# DM1097_IMU.net
KiCad netlist of a schematic drawn in Altium Designer
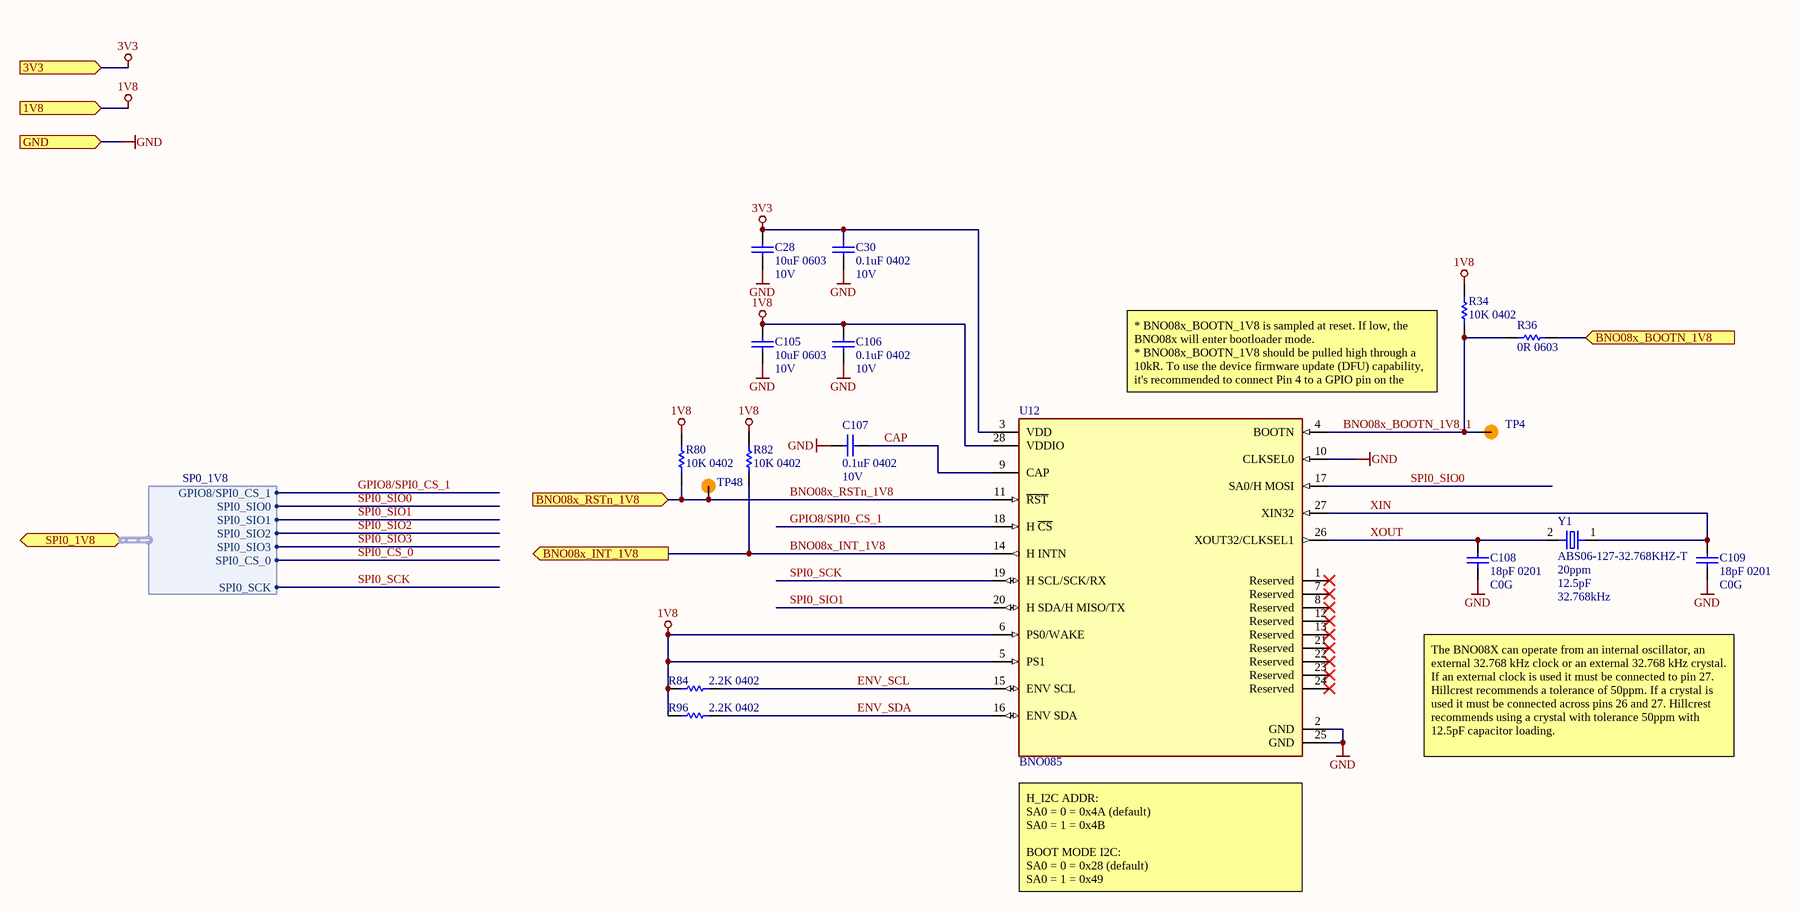
[diagram p0: DM1097_IMU.SchDoc]

(export (version "E")
  (design (tool "Eeschema 10.0.6"))
  (components
    (comp (ref "C28")
      (value "10uF 0603")
      (footprint "CAP_Altium_Vault_Generic:CAPC0603(1608)100_N")
      (description "CAP CER 10UF 10V X5R 0603 20%")
      (fields (field (name "TOLERANCE") "20%") (field (name "VOLTAGE RATING") "10V"))
      (libsource (lib "LuxonisMaster") (part "GRM188R61A106ME69D"))
    )
    (comp (ref "C30")
      (value "0.1uF 0402")
      (footprint "CAP_Altium_Vault_Generic:CAPC0402(1005)70_N")
      (description "CAP CER 0.1UF 10V X7R 0402 5%")
      (fields (field (name "TOLERANCE") "5%") (field (name "VOLTAGE RATING") "10V"))
      (libsource (lib "LuxonisMaster") (part "GRM155R71A104JA01D"))
    )
    (comp (ref "C105")
      (value "10uF 0603")
      (footprint "CAP_Altium_Vault_Generic:CAPC0603(1608)100_N")
      (description "CAP CER 10UF 10V X5R 0603 20%")
      (fields (field (name "TOLERANCE") "20%") (field (name "VOLTAGE RATING") "10V"))
      (libsource (lib "LuxonisMaster") (part "GRM188R61A106ME69D"))
    )
    (comp (ref "C106")
      (value "0.1uF 0402")
      (footprint "CAP_Altium_Vault_Generic:CAPC0402(1005)70_N")
      (description "CAP CER 0.1UF 10V X7R 0402 5%")
      (fields (field (name "TOLERANCE") "5%") (field (name "VOLTAGE RATING") "10V"))
      (libsource (lib "LuxonisMaster") (part "GRM155R71A104JA01D"))
    )
    (comp (ref "C107")
      (value "0.1uF 0402")
      (footprint "CAP_Altium_Vault_Generic:CAPC0402(1005)70_N")
      (description "CAP CER 0.1UF 10V X7R 0402 5%")
      (fields (field (name "TOLERANCE") "5%") (field (name "VOLTAGE RATING") "10V"))
      (libsource (lib "LuxonisMaster") (part "GRM155R71A104JA01D"))
    )
    (comp (ref "C108")
      (value "18pF 0201")
      (footprint "CAPC0201(0603)33_N")
      (description "Cap Ceramic 18pF 25V C0G 1% Pad SMD 0201 125C T/R")
      (fields (field (name "TOLERANCE") "1%") (field (name "DIELECTRIC") "C0G"))
      (libsource (lib "BW1092_R0M0E0") (part "GRM0335C1E180FA01D"))
    )
    (comp (ref "C109")
      (value "18pF 0201")
      (footprint "CAPC0201(0603)33_N")
      (description "Cap Ceramic 18pF 25V C0G 1% Pad SMD 0201 125C T/R")
      (fields (field (name "TOLERANCE") "1%") (field (name "DIELECTRIC") "C0G"))
      (libsource (lib "BW1092_R0M0E0") (part "GRM0335C1E180FA01D"))
    )
    (comp (ref "R34")
      (value "10K 0402")
      (footprint "RES_Altium_Vault_Generic:RESC0402(1005)_N")
      (fields (field (name "TOLERANCE") "1%"))
      (libsource (lib "LuxonisMaster") (part "RC0402FR-1310KL"))
    )
    (comp (ref "R36")
      (value "0R 0603")
      (footprint "RES_Altium_Vault_Generic:RESC0603(1608)_N")
      (fields (field (name "TOLERANCE") "5%"))
      (libsource (lib "LuxonisMaster") (part "CRCW06030000Z0EA"))
    )
    (comp (ref "R80")
      (value "10K 0402")
      (footprint "RES_Altium_Vault_Generic:RESC0402(1005)_N")
      (fields (field (name "TOLERANCE") "1%"))
      (libsource (lib "LuxonisMaster") (part "RC0402FR-1310KL"))
    )
    (comp (ref "R82")
      (value "10K 0402")
      (footprint "RES_Altium_Vault_Generic:RESC0402(1005)_N")
      (fields (field (name "TOLERANCE") "1%"))
      (libsource (lib "LuxonisMaster") (part "RC0402FR-1310KL"))
    )
    (comp (ref "R84")
      (value "2.2K 0402")
      (footprint "RES_Altium_Vault_Generic:RESC0402(1005)_N")
      (description "RES SMD 2.2K OHM 1% 1/16W 0402")
      (fields (field (name "TOLERANCE") "1%"))
      (libsource (lib "LuxonisMaster") (part "RC0402FR-072K2L"))
    )
    (comp (ref "R96")
      (value "2.2K 0402")
      (footprint "RES_Altium_Vault_Generic:RESC0402(1005)_N")
      (description "RES SMD 2.2K OHM 1% 1/16W 0402")
      (fields (field (name "TOLERANCE") "1%"))
      (libsource (lib "LuxonisMaster") (part "RC0402FR-072K2L"))
    )
    (comp (ref "TP4")
      (value "TP100_200_NS")
      (footprint "LuxonisMaster:TP100_200_NS")
      (libsource (lib "LuxonisMaster") (part "TEST_POINT"))
    )
    (comp (ref "TP48")
      (value "TP100_200_NS")
      (footprint "LuxonisMaster:TP100_200_NS")
      (libsource (lib "LuxonisMaster") (part "TEST_POINT"))
    )
    (comp (ref "U12")
      (value "BNO085")
      (footprint "LuxonisMaster:BNO085")
      (description "IMU ACCEL/GYRO/MAG I2C 32BIT")
      (libsource (lib "LuxonisMaster") (part "BNO085"))
    )
    (comp (ref "Y1")
      (value "ABS06-127-32.768KHZ-T")
      (footprint "LuxonisMaster:ABS06-127-32.768KHZ-T")
      (description "CRYSTAL 32.768kHz ±20ppm Crystal 12.5pF 90 kOhms 2-SMD, No Lead")
      (fields
        (field (name "FREQUENCY TOLERANCE") "20ppm")
        (field (name "LOAD CAPACITANCE") "12.5pF")
        (field (name "FREQUENCY") "32.768kHz")
      )
      (libsource (lib "LuxonisMaster") (part "ABS06-127-32.768KHZ-T"))
    )
  )
  (nets
    (net (code "2") (name "/BNO08x_BOOTN_1V8") (class "Default")
      (node (ref "R36") (pin "2") (pinfunction "2_2") (pintype "passive"))
    )
    (net (code "3") (name "/BNO08x_BOOTN_1V8_1") (class "Default")
      (node (ref "R34") (pin "1") (pinfunction "1_1") (pintype "passive"))
      (node (ref "R36") (pin "1") (pinfunction "1_1") (pintype "passive"))
      (node (ref "TP4") (pin "1") (pintype "passive"))
      (node (ref "U12") (pin "4") (pinfunction "BOOTN_4") (pintype "input"))
    )
    (net (code "4") (name "/BNO08x_INT_1V8") (class "Default")
      (node (ref "R82") (pin "1") (pinfunction "1_1") (pintype "passive"))
      (node (ref "U12") (pin "14") (pinfunction "H_INTN_14") (pintype "output"))
    )
    (net (code "5") (name "/BNO08x_RSTn_1V8") (class "Default")
      (node (ref "R80") (pin "1") (pinfunction "1_1") (pintype "passive"))
      (node (ref "TP48") (pin "1") (pintype "passive"))
      (node (ref "U12") (pin "11") (pinfunction "~{RST}_11") (pintype "input"))
    )
    (net (code "6") (name "/CAP") (class "Default")
      (node (ref "C107") (pin "1") (pinfunction "1_1") (pintype "passive"))
      (node (ref "U12") (pin "9") (pinfunction "CAP_9") (pintype "passive"))
    )
    (net (code "7") (name "/ENV_SCL") (class "Default")
      (node (ref "R84") (pin "2") (pinfunction "2_2") (pintype "passive"))
      (node (ref "U12") (pin "15") (pinfunction "ENV_SCL_15") (pintype "bidirectional"))
    )
    (net (code "8") (name "/ENV_SDA") (class "Default")
      (node (ref "R96") (pin "2") (pinfunction "2_2") (pintype "passive"))
      (node (ref "U12") (pin "16") (pinfunction "ENV_SDA_16") (pintype "bidirectional"))
    )
    (net (code "9") (name "/GPIO8{slash}SPI0_CS_1") (class "Default")
      (node (ref "U12") (pin "18") (pinfunction "H_~{CS}_18") (pintype "input"))
    )
    (net (code "11") (name "/SPI0_SCK") (class "Default")
      (node (ref "U12") (pin "19") (pinfunction "H_SCL/SCK/RX_19") (pintype "bidirectional"))
    )
    (net (code "12") (name "/SPI0_SIO0") (class "Default")
      (node (ref "U12") (pin "17") (pinfunction "SA0/H_MOSI_17") (pintype "input"))
    )
    (net (code "13") (name "/SPI0_SIO1") (class "Default")
      (node (ref "U12") (pin "20") (pinfunction "H_SDA/H_MISO/TX_20") (pintype "bidirectional"))
    )
    (net (code "16") (name "/XIN") (class "Default")
      (node (ref "C109") (pin "2") (pinfunction "2_2") (pintype "passive"))
      (node (ref "U12") (pin "27") (pinfunction "XIN32_27") (pintype "input"))
      (node (ref "Y1") (pin "1") (pinfunction "1_1") (pintype "passive"))
    )
    (net (code "17") (name "/XOUT") (class "Default")
      (node (ref "C108") (pin "2") (pinfunction "2_2") (pintype "passive"))
      (node (ref "U12") (pin "26") (pinfunction "XOUT32/CLKSEL1_26") (pintype "output"))
      (node (ref "Y1") (pin "2") (pinfunction "2_2") (pintype "passive"))
    )
    (net (code "19") (name "1V8") (class "Default")
      (node (ref "C105") (pin "2") (pinfunction "2_2") (pintype "passive"))
      (node (ref "C106") (pin "2") (pinfunction "2_2") (pintype "passive"))
      (node (ref "R34") (pin "2") (pinfunction "2_2") (pintype "passive"))
      (node (ref "R80") (pin "2") (pinfunction "2_2") (pintype "passive"))
      (node (ref "R82") (pin "2") (pinfunction "2_2") (pintype "passive"))
      (node (ref "R84") (pin "1") (pinfunction "1_1") (pintype "passive"))
      (node (ref "R96") (pin "1") (pinfunction "1_1") (pintype "passive"))
      (node (ref "U12") (pin "28") (pinfunction "VDDIO_28") (pintype "power_in"))
      (node (ref "U12") (pin "5") (pinfunction "PS1_5") (pintype "input"))
      (node (ref "U12") (pin "6") (pinfunction "PS0/WAKE_6") (pintype "input"))
    )
    (net (code "20") (name "3V3") (class "Default")
      (node (ref "C28") (pin "2") (pinfunction "2_2") (pintype "passive"))
      (node (ref "C30") (pin "2") (pinfunction "2_2") (pintype "passive"))
      (node (ref "U12") (pin "3") (pinfunction "VDD_3") (pintype "power_in"))
    )
    (net (code "21") (name "GND") (class "Default")
      (node (ref "C105") (pin "1") (pinfunction "1_1") (pintype "passive"))
      (node (ref "C106") (pin "1") (pinfunction "1_1") (pintype "passive"))
      (node (ref "C107") (pin "2") (pinfunction "2_2") (pintype "passive"))
      (node (ref "C108") (pin "1") (pinfunction "1_1") (pintype "passive"))
      (node (ref "C109") (pin "1") (pinfunction "1_1") (pintype "passive"))
      (node (ref "C28") (pin "1") (pinfunction "1_1") (pintype "passive"))
      (node (ref "C30") (pin "1") (pinfunction "1_1") (pintype "passive"))
      (node (ref "U12") (pin "10") (pinfunction "CLKSEL0_10") (pintype "input"))
      (node (ref "U12") (pin "2") (pinfunction "GND_2") (pintype "power_in"))
      (node (ref "U12") (pin "25") (pinfunction "GND_25") (pintype "power_in"))
    )
    (net (code "22") (name "unconnected-(U12-Reserved-Pad1)") (class "Default")
      (node (ref "U12") (pin "1") (pinfunction "Reserved_1") (pintype "passive+no_connect"))
    )
    (net (code "23") (name "unconnected-(U12-Reserved-Pad7)") (class "Default")
      (node (ref "U12") (pin "7") (pinfunction "Reserved_7") (pintype "passive+no_connect"))
    )
    (net (code "24") (name "unconnected-(U12-Reserved-Pad8)") (class "Default")
      (node (ref "U12") (pin "8") (pinfunction "Reserved_8") (pintype "passive+no_connect"))
    )
    (net (code "25") (name "unconnected-(U12-Reserved-Pad12)") (class "Default")
      (node (ref "U12") (pin "12") (pinfunction "Reserved_12") (pintype "passive+no_connect"))
    )
    (net (code "26") (name "unconnected-(U12-Reserved-Pad13)") (class "Default")
      (node (ref "U12") (pin "13") (pinfunction "Reserved_13") (pintype "passive+no_connect"))
    )
    (net (code "27") (name "unconnected-(U12-Reserved-Pad21)") (class "Default")
      (node (ref "U12") (pin "21") (pinfunction "Reserved_21") (pintype "passive+no_connect"))
    )
    (net (code "28") (name "unconnected-(U12-Reserved-Pad22)") (class "Default")
      (node (ref "U12") (pin "22") (pinfunction "Reserved_22") (pintype "passive+no_connect"))
    )
    (net (code "29") (name "unconnected-(U12-Reserved-Pad23)") (class "Default")
      (node (ref "U12") (pin "23") (pinfunction "Reserved_23") (pintype "passive+no_connect"))
    )
    (net (code "30") (name "unconnected-(U12-Reserved-Pad24)") (class "Default")
      (node (ref "U12") (pin "24") (pinfunction "Reserved_24") (pintype "passive+no_connect"))
    )
  )
)
